# 12_-_FTDI.net
KiCad netlist of a schematic drawn in Altium Designer
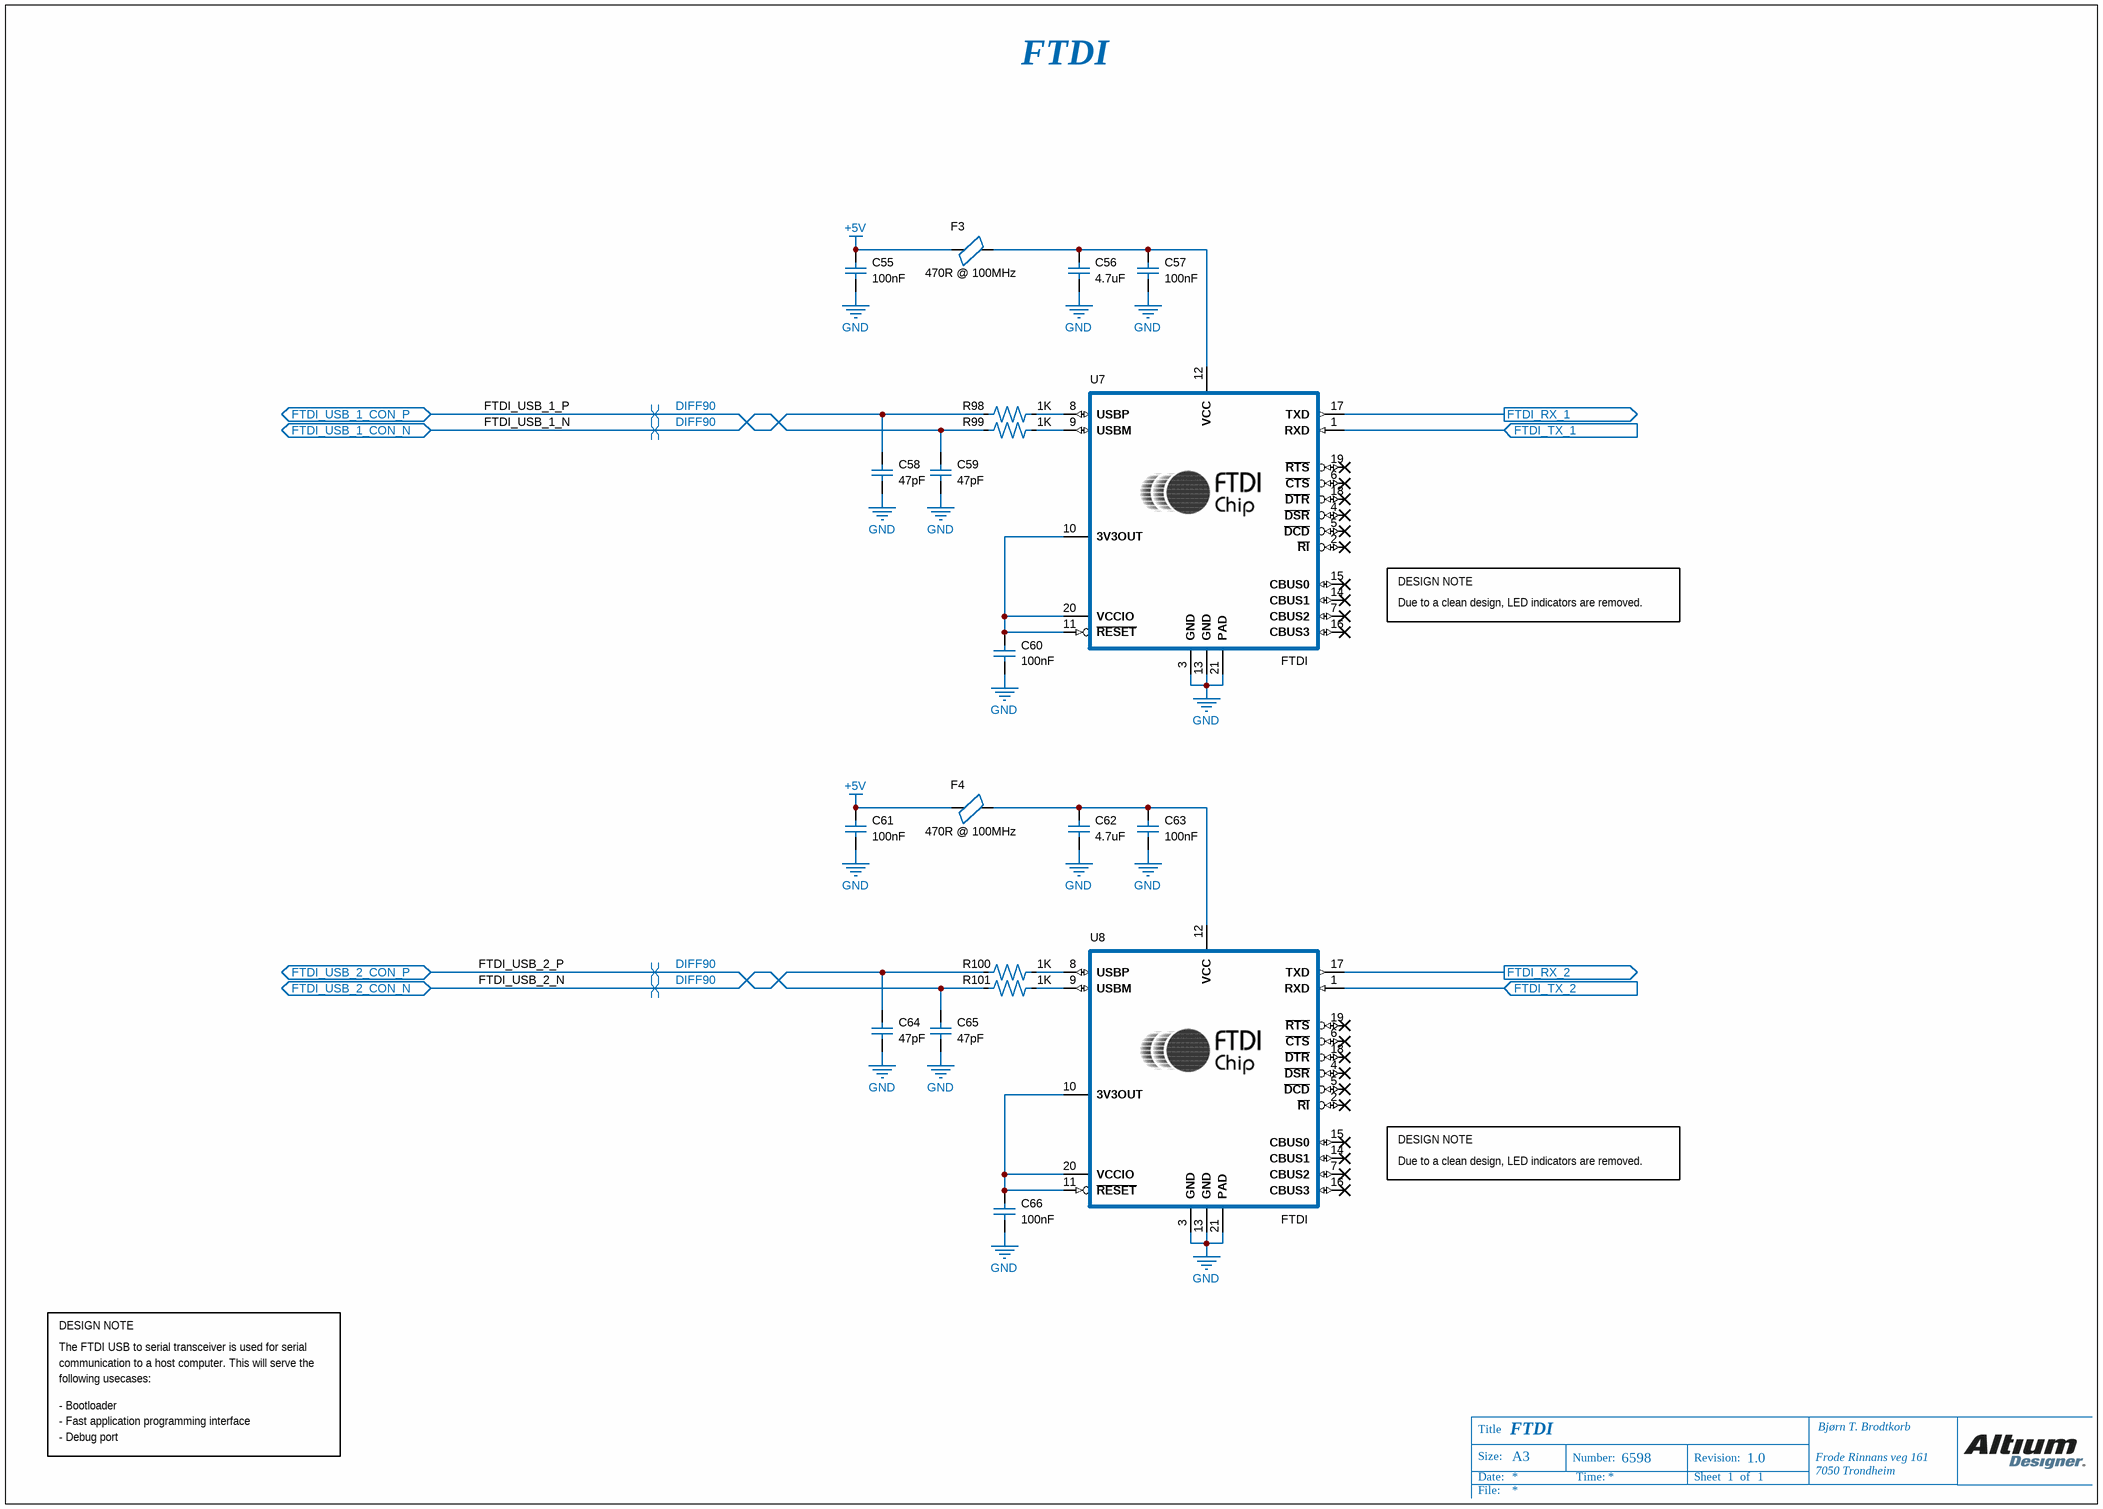
[diagram p0: [12] - FTDI.SchDoc]

(export (version "E")
  (design (tool "Eeschema 10.0.6"))
  (components
    (comp (ref "C55")
      (value "100nF")
      (footprint "C0402")
      (description "C0402")
      (fields (field (name "Comment") "04023C103KAT2A"))
      (libsource (lib "Passive components") (part "04023C103KAT2A"))
    )
    (comp (ref "C56")
      (value "4.7uF")
      (footprint "C0603")
      (description "C0603")
      (fields (field (name "Comment") "02016D104KAT2A"))
      (libsource (lib "Passive components") (part "02016D104KAT2A"))
    )
    (comp (ref "C57")
      (value "100nF")
      (footprint "C0402")
      (description "C0402")
      (fields (field (name "Comment") "04023C103KAT2A"))
      (libsource (lib "Passive components") (part "04023C103KAT2A"))
    )
    (comp (ref "C58")
      (value "47pF")
      (footprint "C0402")
      (description "C0402")
      (fields (field (name "Comment") "04023C103KAT2A"))
      (libsource (lib "Passive components") (part "04023C103KAT2A"))
    )
    (comp (ref "C59")
      (value "47pF")
      (footprint "C0402")
      (description "C0402")
      (fields (field (name "Comment") "04023C103KAT2A"))
      (libsource (lib "Passive components") (part "04023C103KAT2A"))
    )
    (comp (ref "C60")
      (value "100nF")
      (footprint "C0402")
      (description "C0402")
      (fields (field (name "Comment") "04023C103KAT2A"))
      (libsource (lib "Passive components") (part "04023C103KAT2A"))
    )
    (comp (ref "C61")
      (value "100nF")
      (footprint "C0402")
      (description "C0402")
      (fields (field (name "Comment") "04023C103KAT2A"))
      (libsource (lib "Passive components") (part "04023C103KAT2A"))
    )
    (comp (ref "C62")
      (value "4.7uF")
      (footprint "C0603")
      (description "C0603")
      (fields (field (name "Comment") "02016D104KAT2A"))
      (libsource (lib "Passive components") (part "02016D104KAT2A"))
    )
    (comp (ref "C63")
      (value "100nF")
      (footprint "C0402")
      (description "C0402")
      (fields (field (name "Comment") "04023C103KAT2A"))
      (libsource (lib "Passive components") (part "04023C103KAT2A"))
    )
    (comp (ref "C64")
      (value "47pF")
      (footprint "C0402")
      (description "C0402")
      (fields (field (name "Comment") "04023C103KAT2A"))
      (libsource (lib "Passive components") (part "04023C103KAT2A"))
    )
    (comp (ref "C65")
      (value "47pF")
      (footprint "C0402")
      (description "C0402")
      (fields (field (name "Comment") "04023C103KAT2A"))
      (libsource (lib "Passive components") (part "04023C103KAT2A"))
    )
    (comp (ref "C66")
      (value "100nF")
      (footprint "C0402")
      (description "C0402")
      (fields (field (name "Comment") "04023C103KAT2A"))
      (libsource (lib "Passive components") (part "04023C103KAT2A"))
    )
    (comp (ref "F3")
      (value "470R @ 100MHz")
      (footprint "Ferrite bead 0402")
      (description "Ferrite bead 0402")
      (fields (field (name "Comment") "BLM15AG102SN1D"))
      (libsource (lib "Passive components") (part "BLM15AG102SN1D"))
    )
    (comp (ref "F4")
      (value "470R @ 100MHz")
      (footprint "Ferrite bead 0402")
      (description "Ferrite bead 0402")
      (fields (field (name "Comment") "BLM15AG102SN1D"))
      (libsource (lib "Passive components") (part "BLM15AG102SN1D"))
    )
    (comp (ref "R98")
      (value "1K")
      (footprint "R0402")
      (description "R0402")
      (fields (field (name "Comment") "CRCW04020000Z0ED"))
      (libsource (lib "Passive components") (part "CRCW04020000Z0ED"))
    )
    (comp (ref "R99")
      (value "1K")
      (footprint "R0402")
      (description "R0402")
      (fields (field (name "Comment") "CRCW04020000Z0ED"))
      (libsource (lib "Passive components") (part "CRCW04020000Z0ED"))
    )
    (comp (ref "R100")
      (value "1K")
      (footprint "R0402")
      (description "R0402")
      (fields (field (name "Comment") "CRCW04020000Z0ED"))
      (libsource (lib "Passive components") (part "CRCW04020000Z0ED"))
    )
    (comp (ref "R101")
      (value "1K")
      (footprint "R0402")
      (description "R0402")
      (fields (field (name "Comment") "CRCW04020000Z0ED"))
      (libsource (lib "Passive components") (part "CRCW04020000Z0ED"))
    )
    (comp (ref "U7")
      (value "FTDI")
      (footprint "FT231XQ-R")
      (description "USB to RS-232 converter")
      (libsource (lib "IC") (part "FT231XQ-R"))
    )
    (comp (ref "U8")
      (value "FTDI")
      (footprint "FT231XQ-R")
      (description "USB to RS-232 converter")
      (libsource (lib "IC") (part "FT231XQ-R"))
    )
  )
  (nets
    (net (code "1") (name "+5V") (class "Default")
      (node (ref "C55") (pin "1") (pinfunction "1_1") (pintype "passive"))
      (node (ref "C61") (pin "1") (pinfunction "1_1") (pintype "passive"))
      (node (ref "F3") (pin "1") (pinfunction "1_1") (pintype "passive"))
      (node (ref "F4") (pin "1") (pinfunction "1_1") (pintype "passive"))
    )
    (net (code "2") (name "/FTDI_RX_1") (class "Default")
      (node (ref "U7") (pin "17") (pinfunction "TXD_17") (pintype "output"))
    )
    (net (code "3") (name "/FTDI_RX_2") (class "Default")
      (node (ref "U8") (pin "17") (pinfunction "TXD_17") (pintype "output"))
    )
    (net (code "4") (name "/FTDI_TX_1") (class "Default")
      (node (ref "U7") (pin "1") (pinfunction "RXD_1") (pintype "input"))
    )
    (net (code "5") (name "/FTDI_TX_2") (class "Default")
      (node (ref "U8") (pin "1") (pinfunction "RXD_1") (pintype "input"))
    )
    (net (code "6") (name "/FTDI_USB_1_N") (class "Default")
      (node (ref "C59") (pin "1") (pinfunction "1_1") (pintype "passive"))
      (node (ref "R99") (pin "1") (pinfunction "1_1") (pintype "passive"))
    )
    (net (code "7") (name "/FTDI_USB_1_P") (class "Default")
      (node (ref "C58") (pin "1") (pinfunction "1_1") (pintype "passive"))
      (node (ref "R98") (pin "1") (pinfunction "1_1") (pintype "passive"))
    )
    (net (code "8") (name "/FTDI_USB_2_N") (class "Default")
      (node (ref "C65") (pin "1") (pinfunction "1_1") (pintype "passive"))
      (node (ref "R101") (pin "1") (pinfunction "1_1") (pintype "passive"))
    )
    (net (code "9") (name "/FTDI_USB_2_P") (class "Default")
      (node (ref "C64") (pin "1") (pinfunction "1_1") (pintype "passive"))
      (node (ref "R100") (pin "1") (pinfunction "1_1") (pintype "passive"))
    )
    (net (code "10") (name "GND") (class "Default")
      (node (ref "C55") (pin "2") (pinfunction "2_2") (pintype "passive"))
      (node (ref "C56") (pin "2") (pinfunction "2_2") (pintype "passive"))
      (node (ref "C57") (pin "2") (pinfunction "2_2") (pintype "passive"))
      (node (ref "C58") (pin "2") (pinfunction "2_2") (pintype "passive"))
      (node (ref "C59") (pin "2") (pinfunction "2_2") (pintype "passive"))
      (node (ref "C60") (pin "2") (pinfunction "2_2") (pintype "passive"))
      (node (ref "C61") (pin "2") (pinfunction "2_2") (pintype "passive"))
      (node (ref "C62") (pin "2") (pinfunction "2_2") (pintype "passive"))
      (node (ref "C63") (pin "2") (pinfunction "2_2") (pintype "passive"))
      (node (ref "C64") (pin "2") (pinfunction "2_2") (pintype "passive"))
      (node (ref "C65") (pin "2") (pinfunction "2_2") (pintype "passive"))
      (node (ref "C66") (pin "2") (pinfunction "2_2") (pintype "passive"))
      (node (ref "U7") (pin "13") (pinfunction "GND_13") (pintype "power_in"))
      (node (ref "U7") (pin "21") (pinfunction "PAD_21") (pintype "power_in"))
      (node (ref "U7") (pin "3") (pinfunction "GND_3") (pintype "power_in"))
      (node (ref "U8") (pin "13") (pinfunction "GND_13") (pintype "power_in"))
      (node (ref "U8") (pin "21") (pinfunction "PAD_21") (pintype "power_in"))
      (node (ref "U8") (pin "3") (pinfunction "GND_3") (pintype "power_in"))
    )
    (net (code "11") (name "Net-(R98-3)") (class "Default")
      (node (ref "R98") (pin "2") (pinfunction "3_2") (pintype "passive"))
      (node (ref "U7") (pin "8") (pinfunction "USBP_8") (pintype "bidirectional"))
    )
    (net (code "12") (name "Net-(R99-3)") (class "Default")
      (node (ref "R99") (pin "2") (pinfunction "3_2") (pintype "passive"))
      (node (ref "U7") (pin "9") (pinfunction "USBM_9") (pintype "bidirectional"))
    )
    (net (code "13") (name "Net-(R100-3)") (class "Default")
      (node (ref "R100") (pin "2") (pinfunction "3_2") (pintype "passive"))
      (node (ref "U8") (pin "8") (pinfunction "USBP_8") (pintype "bidirectional"))
    )
    (net (code "14") (name "Net-(R101-3)") (class "Default")
      (node (ref "R101") (pin "2") (pinfunction "3_2") (pintype "passive"))
      (node (ref "U8") (pin "9") (pinfunction "USBM_9") (pintype "bidirectional"))
    )
    (net (code "15") (name "Net-(U7-3V3OUT)") (class "Default")
      (node (ref "C60") (pin "1") (pinfunction "1_1") (pintype "passive"))
      (node (ref "U7") (pin "10") (pinfunction "3V3OUT_10") (pintype "power_in"))
      (node (ref "U7") (pin "11") (pinfunction "~{RESET}_11") (pintype "input"))
      (node (ref "U7") (pin "20") (pinfunction "VCCIO_20") (pintype "power_in"))
    )
    (net (code "16") (name "Net-(U7-VCC)") (class "Default")
      (node (ref "C56") (pin "1") (pinfunction "1_1") (pintype "passive"))
      (node (ref "C57") (pin "1") (pinfunction "1_1") (pintype "passive"))
      (node (ref "F3") (pin "2") (pinfunction "2_2") (pintype "passive"))
      (node (ref "U7") (pin "12") (pinfunction "VCC_12") (pintype "power_in"))
    )
    (net (code "17") (name "Net-(U8-3V3OUT)") (class "Default")
      (node (ref "C66") (pin "1") (pinfunction "1_1") (pintype "passive"))
      (node (ref "U8") (pin "10") (pinfunction "3V3OUT_10") (pintype "power_in"))
      (node (ref "U8") (pin "11") (pinfunction "~{RESET}_11") (pintype "input"))
      (node (ref "U8") (pin "20") (pinfunction "VCCIO_20") (pintype "power_in"))
    )
    (net (code "18") (name "Net-(U8-VCC)") (class "Default")
      (node (ref "C62") (pin "1") (pinfunction "1_1") (pintype "passive"))
      (node (ref "C63") (pin "1") (pinfunction "1_1") (pintype "passive"))
      (node (ref "F4") (pin "2") (pinfunction "2_2") (pintype "passive"))
      (node (ref "U8") (pin "12") (pinfunction "VCC_12") (pintype "power_in"))
    )
    (net (code "19") (name "unconnected-(U7-CBUS0-Pad15)") (class "Default")
      (node (ref "U7") (pin "15") (pinfunction "CBUS0_15") (pintype "bidirectional+no_connect"))
    )
    (net (code "20") (name "unconnected-(U7-CBUS1-Pad14)") (class "Default")
      (node (ref "U7") (pin "14") (pinfunction "CBUS1_14") (pintype "bidirectional+no_connect"))
    )
    (net (code "21") (name "unconnected-(U7-CBUS2-Pad7)") (class "Default")
      (node (ref "U7") (pin "7") (pinfunction "CBUS2_7") (pintype "bidirectional+no_connect"))
    )
    (net (code "22") (name "unconnected-(U7-CBUS3-Pad16)") (class "Default")
      (node (ref "U7") (pin "16") (pinfunction "CBUS3_16") (pintype "bidirectional+no_connect"))
    )
    (net (code "23") (name "unconnected-(U7-~{CTS}-Pad6)") (class "Default")
      (node (ref "U7") (pin "6") (pinfunction "~{CTS}_6") (pintype "bidirectional+no_connect"))
    )
    (net (code "24") (name "unconnected-(U7-~{DCD}-Pad5)") (class "Default")
      (node (ref "U7") (pin "5") (pinfunction "~{DCD}_5") (pintype "bidirectional+no_connect"))
    )
    (net (code "25") (name "unconnected-(U7-~{DSR}-Pad4)") (class "Default")
      (node (ref "U7") (pin "4") (pinfunction "~{DSR}_4") (pintype "bidirectional+no_connect"))
    )
    (net (code "26") (name "unconnected-(U7-~{DTR}-Pad18)") (class "Default")
      (node (ref "U7") (pin "18") (pinfunction "~{DTR}_18") (pintype "bidirectional+no_connect"))
    )
    (net (code "27") (name "unconnected-(U7-~{RI}-Pad2)") (class "Default")
      (node (ref "U7") (pin "2") (pinfunction "~{RI}_2") (pintype "bidirectional+no_connect"))
    )
    (net (code "28") (name "unconnected-(U7-~{RTS}-Pad19)") (class "Default")
      (node (ref "U7") (pin "19") (pinfunction "~{RTS}_19") (pintype "bidirectional+no_connect"))
    )
    (net (code "29") (name "unconnected-(U8-CBUS0-Pad15)") (class "Default")
      (node (ref "U8") (pin "15") (pinfunction "CBUS0_15") (pintype "bidirectional+no_connect"))
    )
    (net (code "30") (name "unconnected-(U8-CBUS1-Pad14)") (class "Default")
      (node (ref "U8") (pin "14") (pinfunction "CBUS1_14") (pintype "bidirectional+no_connect"))
    )
    (net (code "31") (name "unconnected-(U8-CBUS2-Pad7)") (class "Default")
      (node (ref "U8") (pin "7") (pinfunction "CBUS2_7") (pintype "bidirectional+no_connect"))
    )
    (net (code "32") (name "unconnected-(U8-CBUS3-Pad16)") (class "Default")
      (node (ref "U8") (pin "16") (pinfunction "CBUS3_16") (pintype "bidirectional+no_connect"))
    )
    (net (code "33") (name "unconnected-(U8-~{CTS}-Pad6)") (class "Default")
      (node (ref "U8") (pin "6") (pinfunction "~{CTS}_6") (pintype "bidirectional+no_connect"))
    )
    (net (code "34") (name "unconnected-(U8-~{DCD}-Pad5)") (class "Default")
      (node (ref "U8") (pin "5") (pinfunction "~{DCD}_5") (pintype "bidirectional+no_connect"))
    )
    (net (code "35") (name "unconnected-(U8-~{DSR}-Pad4)") (class "Default")
      (node (ref "U8") (pin "4") (pinfunction "~{DSR}_4") (pintype "bidirectional+no_connect"))
    )
    (net (code "36") (name "unconnected-(U8-~{DTR}-Pad18)") (class "Default")
      (node (ref "U8") (pin "18") (pinfunction "~{DTR}_18") (pintype "bidirectional+no_connect"))
    )
    (net (code "37") (name "unconnected-(U8-~{RI}-Pad2)") (class "Default")
      (node (ref "U8") (pin "2") (pinfunction "~{RI}_2") (pintype "bidirectional+no_connect"))
    )
    (net (code "38") (name "unconnected-(U8-~{RTS}-Pad19)") (class "Default")
      (node (ref "U8") (pin "19") (pinfunction "~{RTS}_19") (pintype "bidirectional+no_connect"))
    )
  )
)
